# deneme_yedek.net
KiCad netlist of a schematic drawn in Altium Designer
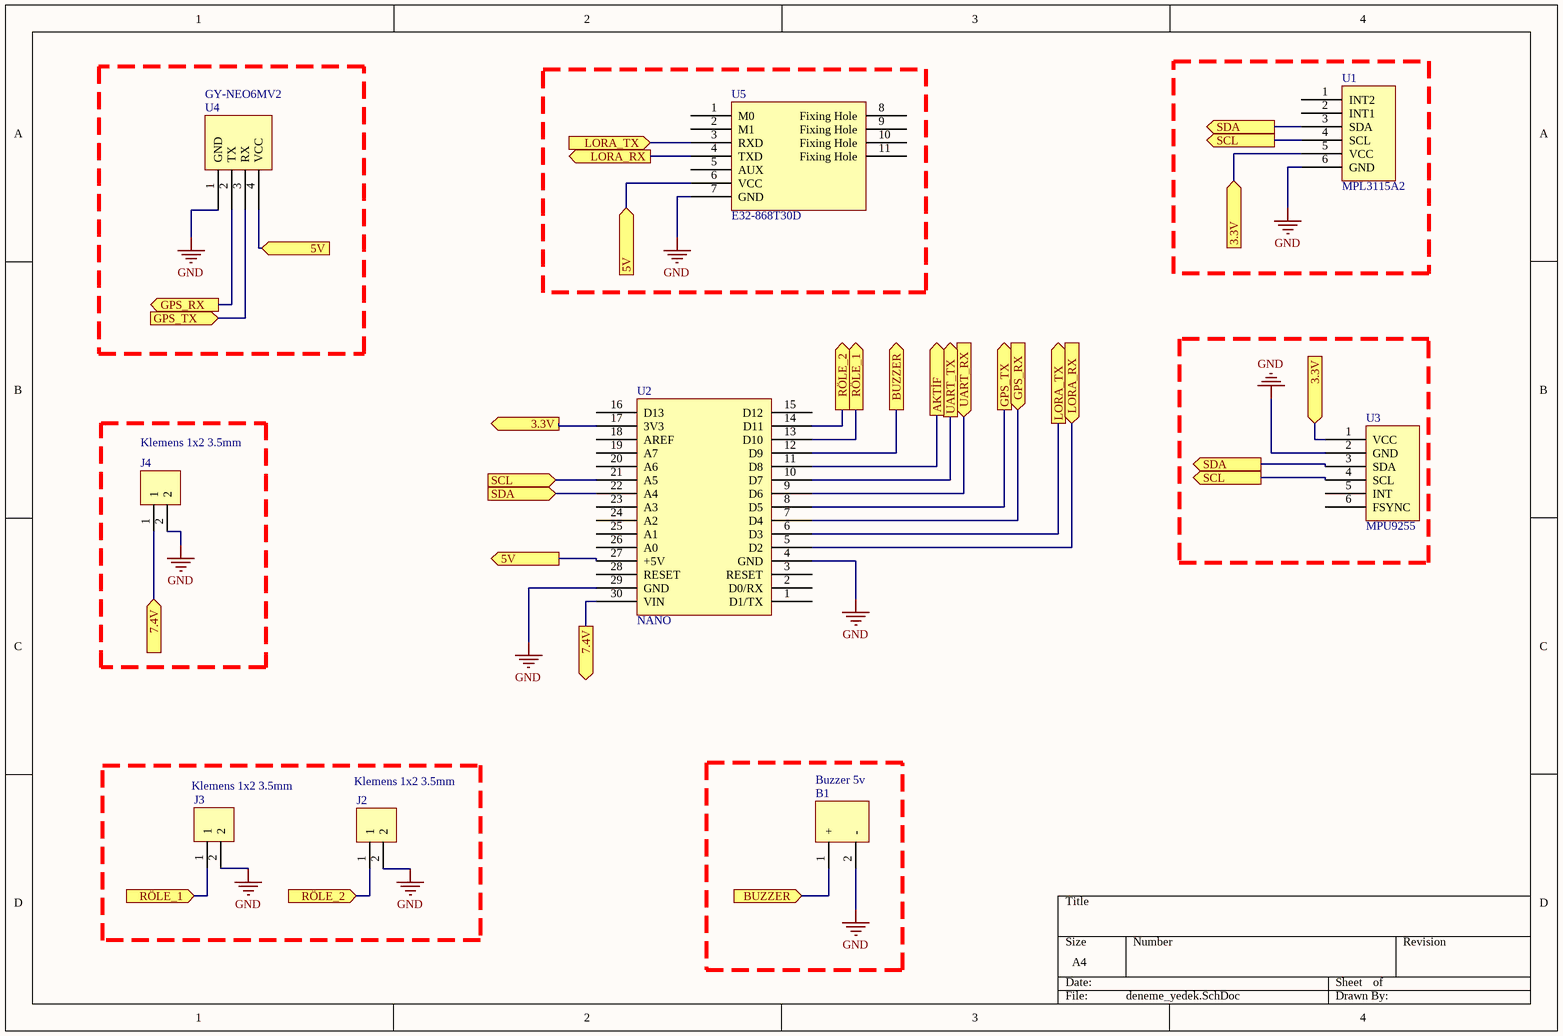
[diagram p0: deneme_yedek.SchDoc]

(export (version "E")
  (design (tool "Eeschema 10.0.6"))
  (components
    (comp (ref "B1")
      (value "Buzzer 5v")
      (footprint "Buzzer 5v")
      (libsource (lib "deneme") (part "Buzzer 5v"))
    )
    (comp (ref "J2")
      (value "Klemens 1x2 3.5mm")
      (footprint "Klemens 1x2 - 3.5mm")
      (libsource (lib "deneme") (part "Klemens 1x2 3.5mm"))
    )
    (comp (ref "J3")
      (value "Klemens 1x2 3.5mm")
      (footprint "Klemens 1x2 - 3.5mm")
      (libsource (lib "deneme") (part "Klemens 1x2 3.5mm"))
    )
    (comp (ref "J4")
      (value "Klemens 1x2 3.5mm")
      (footprint "Klemens 1x2 - 3.5mm")
      (libsource (lib "deneme_yedek") (part "Klemens 1x2 3.5mm"))
    )
    (comp (ref "U1")
      (value "MPL3115A2")
      (footprint "MPL3115A2")
      (libsource (lib "deneme_yedek") (part "MPL3115A2"))
    )
    (comp (ref "U2") (value "NANO") (footprint "nano") (libsource (lib "deneme") (part "NANO")))
    (comp (ref "U3")
      (value "MPU9255")
      (footprint "MPU9255")
      (libsource (lib "deneme_yedek") (part "MPU9255"))
    )
    (comp (ref "U4")
      (value "GY-NEO6MV2")
      (footprint "GY-NEO6MV2")
      (libsource (lib "deneme") (part "GY-NEO6MV2"))
    )
    (comp (ref "U5")
      (value "E32-868T30D")
      (footprint "E32-868T30D")
      (libsource (lib "deneme") (part "E32-868T30D"))
    )
  )
  (nets
    (net (code "1") (name "/3.3V") (class "Default")
      (node (ref "U1") (pin "5") (pinfunction "VCC_5") (pintype "passive"))
      (node (ref "U2") (pin "17") (pinfunction "3V3_17") (pintype "passive"))
      (node (ref "U3") (pin "1") (pinfunction "VCC_1") (pintype "passive"))
    )
    (net (code "2") (name "/5V") (class "Default")
      (node (ref "U2") (pin "27") (pinfunction "+5V_27") (pintype "passive"))
      (node (ref "U4") (pin "4") (pinfunction "VCC_4") (pintype "passive"))
      (node (ref "U5") (pin "6") (pinfunction "VCC_6") (pintype "passive"))
    )
    (net (code "3") (name "/7.4V") (class "Default")
      (node (ref "J4") (pin "1") (pinfunction "1_1") (pintype "passive"))
      (node (ref "U2") (pin "30") (pinfunction "VIN_30") (pintype "passive"))
    )
    (net (code "4") (name "/AKTİF") (class "Default")
      (node (ref "U2") (pin "11") (pinfunction "D8_11") (pintype "passive"))
    )
    (net (code "5") (name "/BUZZER") (class "Default")
      (node (ref "B1") (pin "1") (pinfunction "+_1") (pintype "passive"))
      (node (ref "U2") (pin "12") (pinfunction "D9_12") (pintype "passive"))
    )
    (net (code "6") (name "/GPS_RX") (class "Default")
      (node (ref "U2") (pin "7") (pinfunction "D4_7") (pintype "passive"))
      (node (ref "U4") (pin "2") (pinfunction "TX_2") (pintype "passive"))
    )
    (net (code "7") (name "/GPS_TX") (class "Default")
      (node (ref "U2") (pin "8") (pinfunction "D5_8") (pintype "passive"))
      (node (ref "U4") (pin "3") (pinfunction "RX_3") (pintype "passive"))
    )
    (net (code "8") (name "/LORA_RX") (class "Default")
      (node (ref "U2") (pin "5") (pinfunction "D2_5") (pintype "passive"))
      (node (ref "U5") (pin "4") (pinfunction "TXD_4") (pintype "passive"))
    )
    (net (code "9") (name "/LORA_TX") (class "Default")
      (node (ref "U2") (pin "6") (pinfunction "D3_6") (pintype "passive"))
      (node (ref "U5") (pin "3") (pinfunction "RXD_3") (pintype "passive"))
    )
    (net (code "10") (name "/RÖLE_1") (class "Default")
      (node (ref "J3") (pin "1") (pinfunction "1_1") (pintype "passive"))
      (node (ref "U2") (pin "13") (pinfunction "D10_13") (pintype "passive"))
    )
    (net (code "11") (name "/RÖLE_2") (class "Default")
      (node (ref "J2") (pin "1") (pinfunction "1_1") (pintype "passive"))
      (node (ref "U2") (pin "14") (pinfunction "D11_14") (pintype "passive"))
    )
    (net (code "12") (name "/SCL") (class "Default")
      (node (ref "U1") (pin "4") (pinfunction "SCL_4") (pintype "passive"))
      (node (ref "U2") (pin "21") (pinfunction "A5_21") (pintype "passive"))
      (node (ref "U3") (pin "4") (pinfunction "SCL_4") (pintype "passive"))
    )
    (net (code "13") (name "/SDA") (class "Default")
      (node (ref "U1") (pin "3") (pinfunction "SDA_3") (pintype "passive"))
      (node (ref "U2") (pin "22") (pinfunction "A4_22") (pintype "passive"))
      (node (ref "U3") (pin "3") (pinfunction "SDA_3") (pintype "passive"))
    )
    (net (code "14") (name "/UART_RX") (class "Default")
      (node (ref "U2") (pin "9") (pinfunction "D6_9") (pintype "passive"))
    )
    (net (code "15") (name "/UART_TX") (class "Default")
      (node (ref "U2") (pin "10") (pinfunction "D7_10") (pintype "passive"))
    )
    (net (code "16") (name "GND") (class "Default")
      (node (ref "B1") (pin "2") (pinfunction "-_2") (pintype "passive"))
      (node (ref "J2") (pin "2") (pinfunction "2_2") (pintype "passive"))
      (node (ref "J3") (pin "2") (pinfunction "2_2") (pintype "passive"))
      (node (ref "J4") (pin "2") (pinfunction "2_2") (pintype "passive"))
      (node (ref "U1") (pin "6") (pinfunction "GND_6") (pintype "passive"))
      (node (ref "U2") (pin "29") (pinfunction "GND_29") (pintype "passive"))
      (node (ref "U2") (pin "4") (pinfunction "GND_4") (pintype "passive"))
      (node (ref "U3") (pin "2") (pinfunction "GND_2") (pintype "passive"))
      (node (ref "U4") (pin "1") (pinfunction "GND_1") (pintype "passive"))
      (node (ref "U5") (pin "7") (pinfunction "GND_7") (pintype "passive"))
    )
    (net (code "17") (name "unconnected-(U1-INT1-Pad2)") (class "Default")
      (node (ref "U1") (pin "2") (pinfunction "INT1_2") (pintype "passive"))
    )
    (net (code "18") (name "unconnected-(U1-INT2-Pad1)") (class "Default")
      (node (ref "U1") (pin "1") (pinfunction "INT2_1") (pintype "passive"))
    )
    (net (code "19") (name "unconnected-(U2-A0-Pad26)") (class "Default")
      (node (ref "U2") (pin "26") (pinfunction "A0_26") (pintype "passive"))
    )
    (net (code "20") (name "unconnected-(U2-A1-Pad25)") (class "Default")
      (node (ref "U2") (pin "25") (pinfunction "A1_25") (pintype "passive"))
    )
    (net (code "21") (name "unconnected-(U2-A2-Pad24)") (class "Default")
      (node (ref "U2") (pin "24") (pinfunction "A2_24") (pintype "passive"))
    )
    (net (code "22") (name "unconnected-(U2-A3-Pad23)") (class "Default")
      (node (ref "U2") (pin "23") (pinfunction "A3_23") (pintype "passive"))
    )
    (net (code "23") (name "unconnected-(U2-A6-Pad20)") (class "Default")
      (node (ref "U2") (pin "20") (pinfunction "A6_20") (pintype "passive"))
    )
    (net (code "24") (name "unconnected-(U2-A7-Pad19)") (class "Default")
      (node (ref "U2") (pin "19") (pinfunction "A7_19") (pintype "passive"))
    )
    (net (code "25") (name "unconnected-(U2-AREF-Pad18)") (class "Default")
      (node (ref "U2") (pin "18") (pinfunction "AREF_18") (pintype "passive"))
    )
    (net (code "26") (name "unconnected-(U2-D0{slash}RX-Pad2)") (class "Default")
      (node (ref "U2") (pin "2") (pinfunction "D0/RX_2") (pintype "passive"))
    )
    (net (code "27") (name "unconnected-(U2-D1{slash}TX-Pad1)") (class "Default")
      (node (ref "U2") (pin "1") (pinfunction "D1/TX_1") (pintype "passive"))
    )
    (net (code "28") (name "unconnected-(U2-D12-Pad15)") (class "Default")
      (node (ref "U2") (pin "15") (pinfunction "D12_15") (pintype "passive"))
    )
    (net (code "29") (name "unconnected-(U2-D13-Pad16)") (class "Default")
      (node (ref "U2") (pin "16") (pinfunction "D13_16") (pintype "passive"))
    )
    (net (code "30") (name "unconnected-(U2-RESET-Pad3)") (class "Default")
      (node (ref "U2") (pin "3") (pinfunction "RESET_3") (pintype "passive"))
    )
    (net (code "31") (name "unconnected-(U2-RESET-Pad28)") (class "Default")
      (node (ref "U2") (pin "28") (pinfunction "RESET_28") (pintype "passive"))
    )
    (net (code "32") (name "unconnected-(U3-FSYNC-Pad6)") (class "Default")
      (node (ref "U3") (pin "6") (pinfunction "FSYNC_6") (pintype "passive"))
    )
    (net (code "33") (name "unconnected-(U3-INT-Pad5)") (class "Default")
      (node (ref "U3") (pin "5") (pinfunction "INT_5") (pintype "passive"))
    )
    (net (code "34") (name "unconnected-(U5-AUX-Pad5)") (class "Default")
      (node (ref "U5") (pin "5") (pinfunction "AUX_5") (pintype "passive"))
    )
    (net (code "35") (name "unconnected-(U5-Fixing_Hole-Pad8)") (class "Default")
      (node (ref "U5") (pin "8") (pinfunction "Fixing_Hole_8") (pintype "passive"))
    )
    (net (code "36") (name "unconnected-(U5-Fixing_Hole-Pad9)") (class "Default")
      (node (ref "U5") (pin "9") (pinfunction "Fixing_Hole_9") (pintype "passive"))
    )
    (net (code "37") (name "unconnected-(U5-Fixing_Hole-Pad10)") (class "Default")
      (node (ref "U5") (pin "10") (pinfunction "Fixing_Hole_10") (pintype "passive"))
    )
    (net (code "38") (name "unconnected-(U5-Fixing_Hole-Pad11)") (class "Default")
      (node (ref "U5") (pin "11") (pinfunction "Fixing_Hole_11") (pintype "passive"))
    )
    (net (code "39") (name "unconnected-(U5-M0-Pad1)") (class "Default")
      (node (ref "U5") (pin "1") (pinfunction "M0_1") (pintype "passive"))
    )
    (net (code "40") (name "unconnected-(U5-M1-Pad2)") (class "Default")
      (node (ref "U5") (pin "2") (pinfunction "M1_2") (pintype "passive"))
    )
  )
)
